# Adafruit_Feather_M0_Adalogger.net
KiCad netlist of a schematic drawn in EAGLE
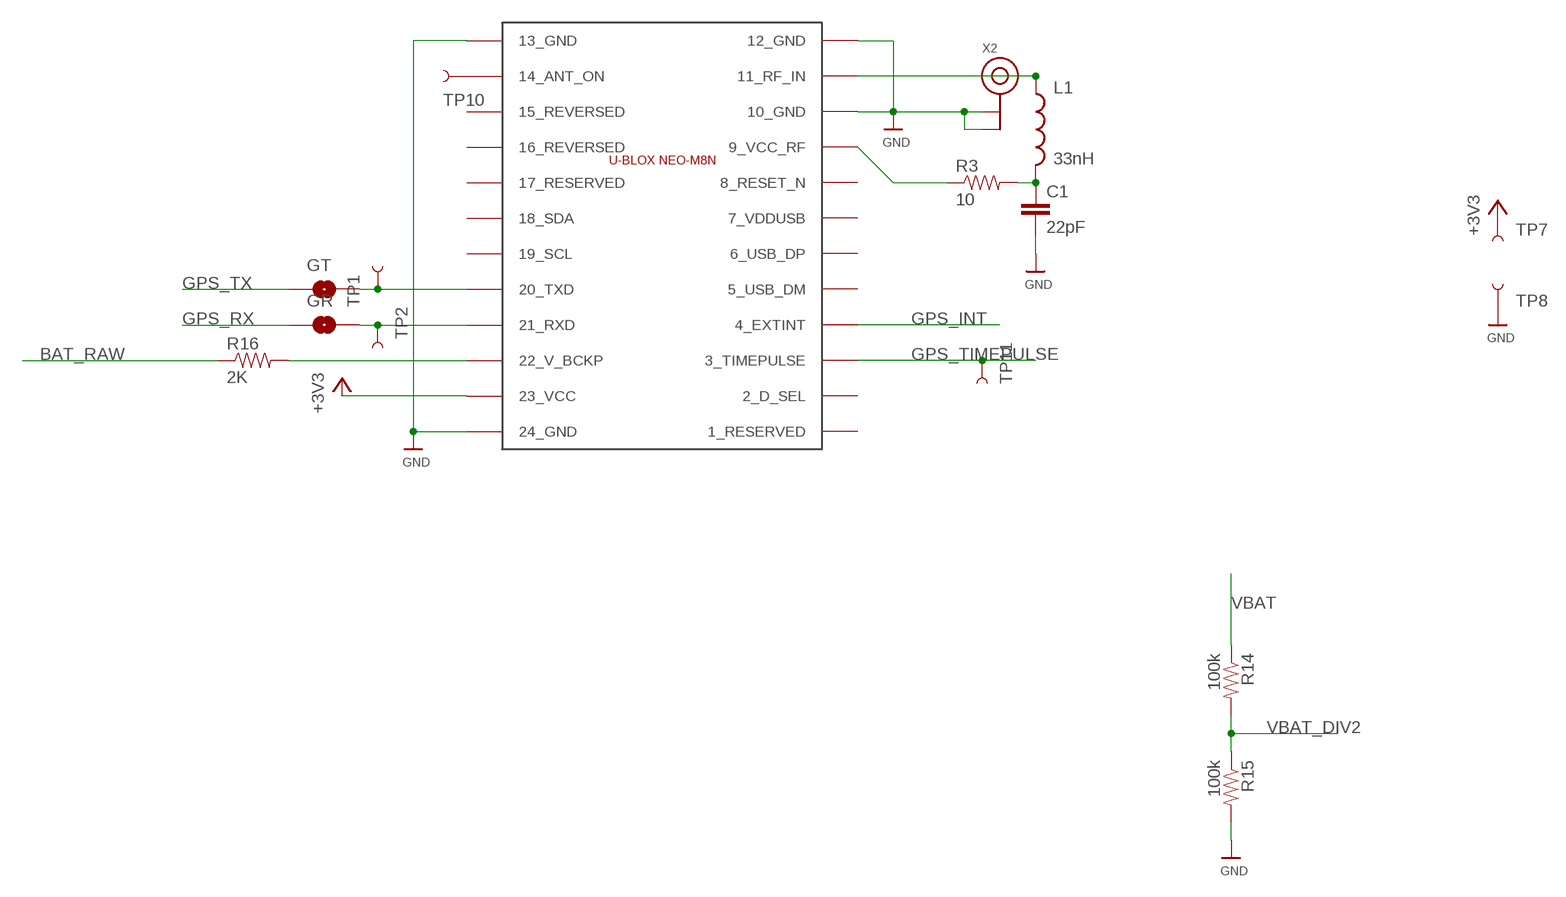
[diagram p0: schematic, sheet 1, part 1 of 2]
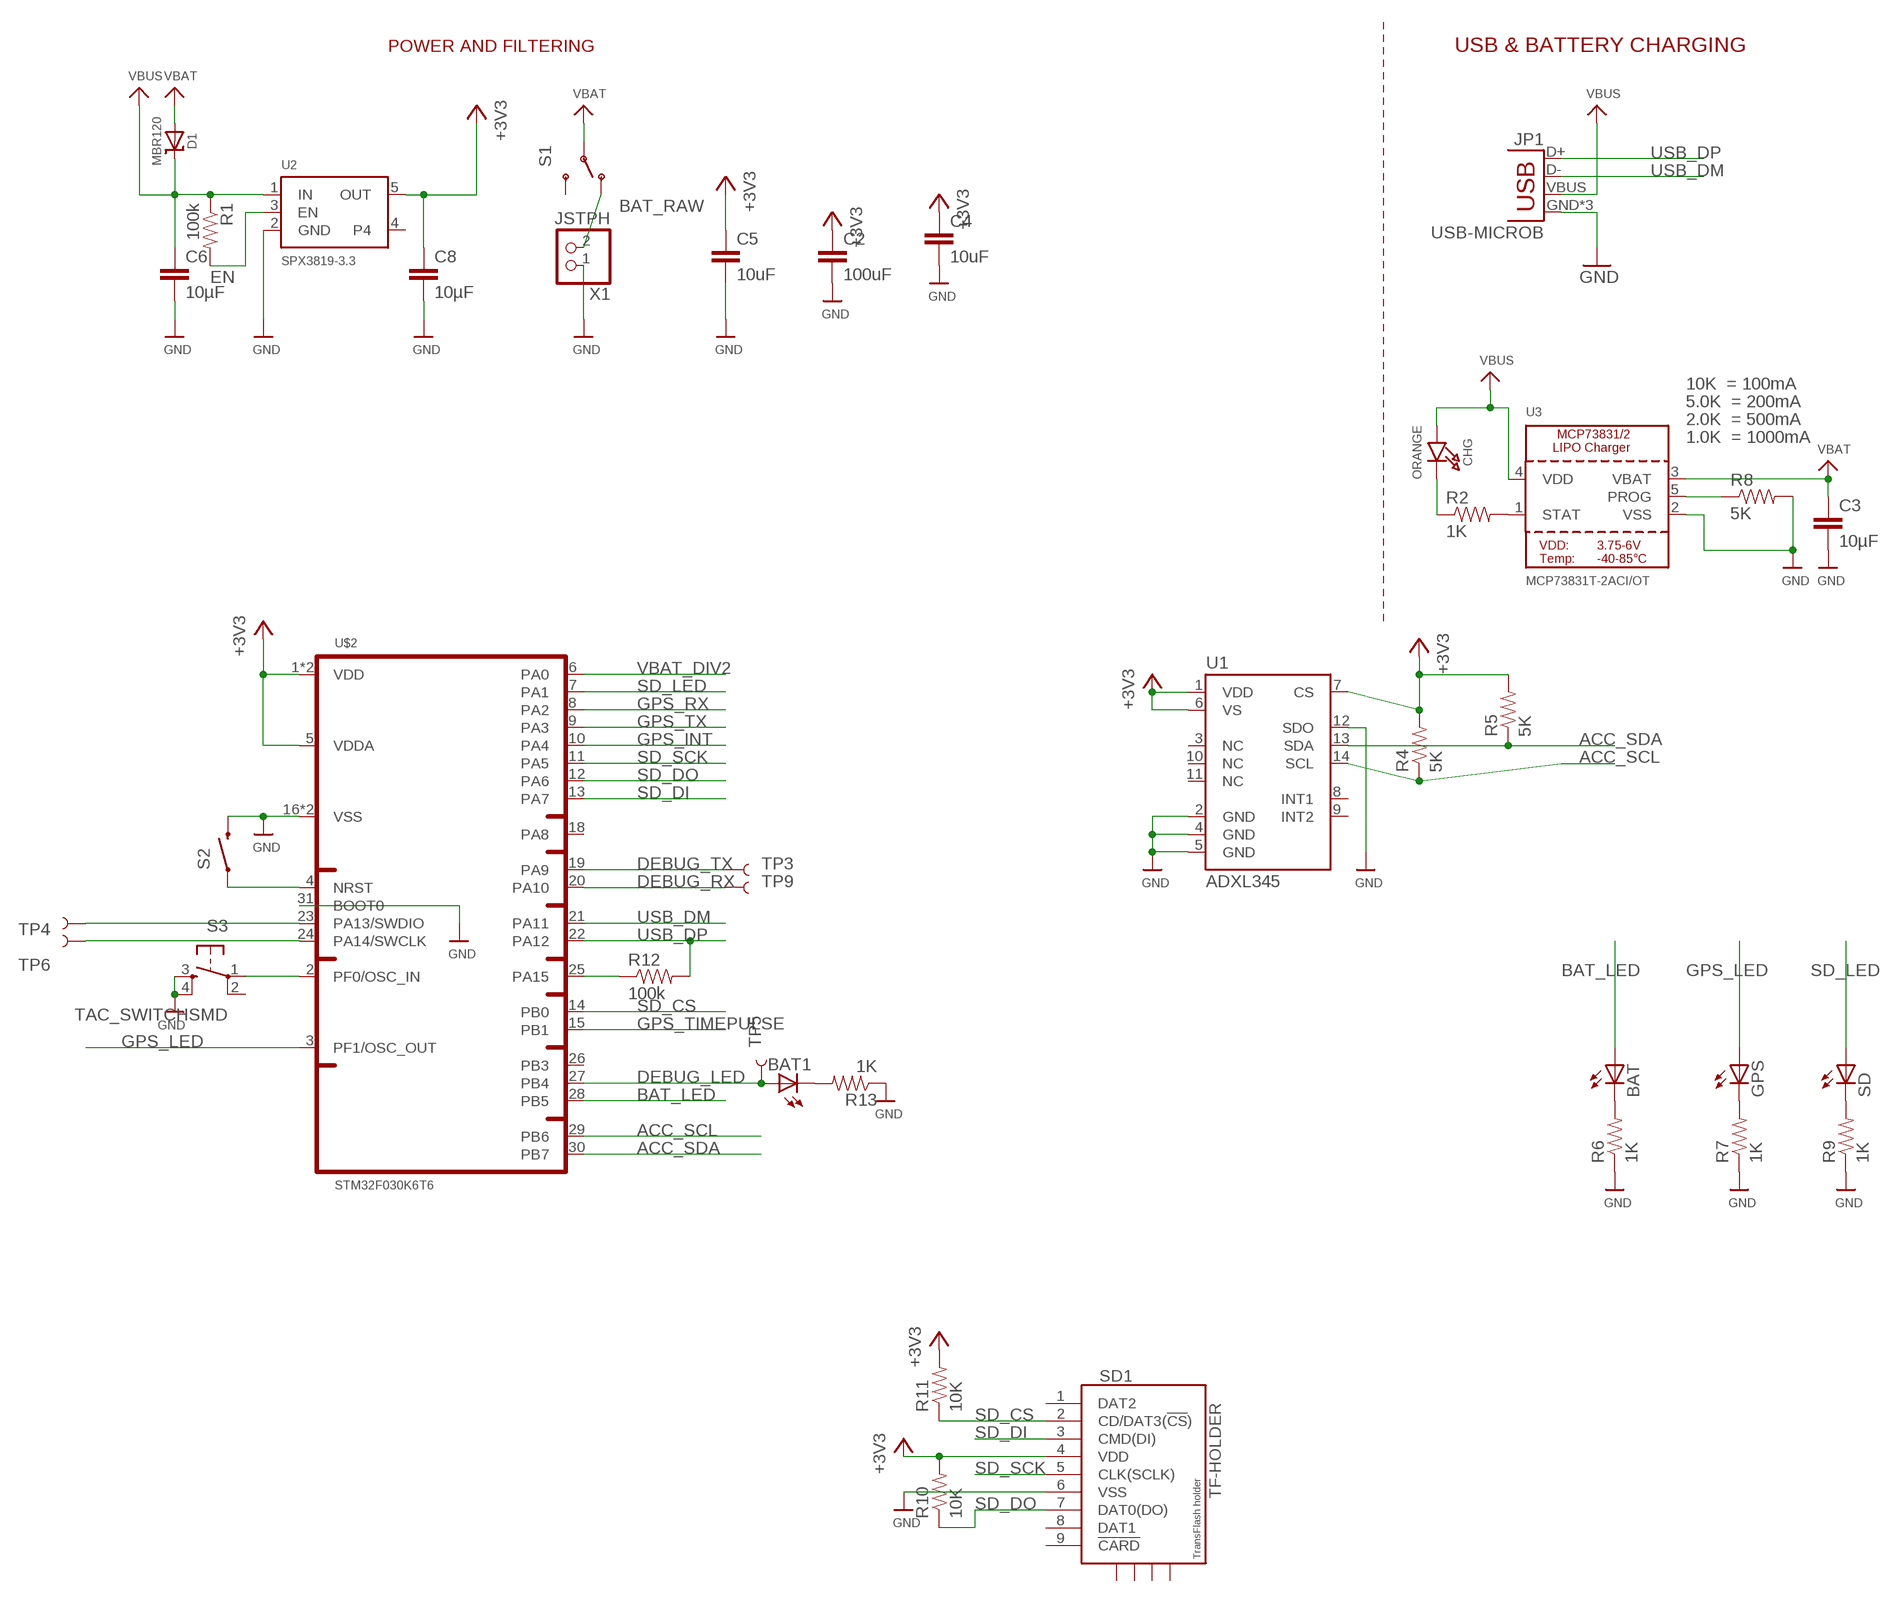
[diagram p1: schematic, sheet 1, part 2 of 2]

(export (version "E")
  (design (tool "Eeschema 10.0.6"))
  (components
    (comp (ref "BAT")
      (value "LEDCHIPLED_0805")
      (footprint "eagle-import:CHIPLED_0805")
      (libsource (lib "eagle-import") (part "LEDCHIPLED_0805"))
    )
    (comp (ref "BAT1")
      (value "LEDCHIPLED_0805")
      (footprint "eagle-import:CHIPLED_0805")
      (libsource (lib "eagle-import") (part "LEDCHIPLED_0805"))
    )
    (comp (ref "C1")
      (value "22pF")
      (footprint "eagle-import:0805")
      (libsource (lib "eagle-import") (part "CAP0805"))
    )
    (comp (ref "C2")
      (value "100uF")
      (footprint "eagle-import:1210")
      (libsource (lib "eagle-import") (part "100UF6.3V20%(1210)"))
    )
    (comp (ref "C3")
      (value "10µF")
      (footprint "eagle-import:0805")
      (libsource (lib "eagle-import") (part "CAP0805"))
    )
    (comp (ref "C4")
      (value "10uF")
      (footprint "eagle-import:0805")
      (libsource (lib "eagle-import") (part "CAP0805"))
    )
    (comp (ref "C5")
      (value "10uF")
      (footprint "eagle-import:0805")
      (libsource (lib "eagle-import") (part "CAP0805"))
    )
    (comp (ref "C6")
      (value "10µF")
      (footprint "eagle-import:0805")
      (libsource (lib "eagle-import") (part "CAP0805"))
    )
    (comp (ref "C8")
      (value "10µF")
      (footprint "eagle-import:0805")
      (libsource (lib "eagle-import") (part "CAP0805"))
    )
    (comp (ref "CHG")
      (value "ORANGE")
      (footprint "eagle-import:CHIPLED_0805_NOOUTLINE")
      (libsource (lib "eagle-import") (part "LED0805_NOOUTLINE"))
    )
    (comp (ref "D1")
      (value "MBR120")
      (footprint "eagle-import:SOD-123")
      (libsource (lib "eagle-import") (part "DIODE-SCHOTTKYSOD-123"))
    )
    (comp (ref "DEKU1")
      (value "UBLOX_NEO-M8N")
      (footprint "eagle-import:UBLOX_NEO-M8N")
      (libsource (lib "eagle-import") (part "UBLOX_NEO-M8N"))
    )
    (comp (ref "GPS")
      (value "LEDCHIPLED_0805")
      (footprint "eagle-import:CHIPLED_0805")
      (libsource (lib "eagle-import") (part "LEDCHIPLED_0805"))
    )
    (comp (ref "GR")
      (value "JUMPER-PAD-2-NO")
      (footprint "eagle-import:PAD-JUMPER-2-NO_NO_SILK")
      (libsource (lib "eagle-import") (part "JUMPER-PAD-2-NO"))
    )
    (comp (ref "GT")
      (value "JUMPER-PAD-2-NO")
      (footprint "eagle-import:PAD-JUMPER-2-NO_NO_SILK")
      (libsource (lib "eagle-import") (part "JUMPER-PAD-2-NO"))
    )
    (comp (ref "JP1")
      (value "USB-MICROB")
      (footprint "eagle-import:USB-MICROB")
      (libsource (lib "eagle-import") (part "USB-MICROB"))
    )
    (comp (ref "L1")
      (value "33nH")
      (footprint "eagle-import:0805")
      (libsource (lib "eagle-import") (part "INDUCTOR0805"))
    )
    (comp (ref "R1")
      (value "100k")
      (footprint "eagle-import:0805")
      (libsource (lib "eagle-import") (part "RESISTOR0805-RES"))
    )
    (comp (ref "R2")
      (value "1K")
      (footprint "eagle-import:0805")
      (libsource (lib "eagle-import") (part "RESISTOR0805-RES"))
    )
    (comp (ref "R3")
      (value "10")
      (footprint "eagle-import:0805")
      (libsource (lib "eagle-import") (part "RESISTOR0805-RES"))
    )
    (comp (ref "R4")
      (value "5K")
      (footprint "eagle-import:0805")
      (libsource (lib "eagle-import") (part "RESISTOR0805-RES"))
    )
    (comp (ref "R5")
      (value "5K")
      (footprint "eagle-import:0805")
      (libsource (lib "eagle-import") (part "RESISTOR0805-RES"))
    )
    (comp (ref "R6")
      (value "1K")
      (footprint "eagle-import:0805")
      (libsource (lib "eagle-import") (part "RESISTOR0805-RES"))
    )
    (comp (ref "R7")
      (value "1K")
      (footprint "eagle-import:0805")
      (libsource (lib "eagle-import") (part "RESISTOR0805-RES"))
    )
    (comp (ref "R8")
      (value "5K")
      (footprint "eagle-import:0805")
      (libsource (lib "eagle-import") (part "RESISTOR0805-RES"))
    )
    (comp (ref "R9")
      (value "1K")
      (footprint "eagle-import:0805")
      (libsource (lib "eagle-import") (part "RESISTOR0805-RES"))
    )
    (comp (ref "R10")
      (value "10K")
      (footprint "eagle-import:0805")
      (libsource (lib "eagle-import") (part "RESISTOR0805-RES"))
    )
    (comp (ref "R11")
      (value "10K")
      (footprint "eagle-import:0805")
      (libsource (lib "eagle-import") (part "RESISTOR0805-RES"))
    )
    (comp (ref "R12")
      (value "100k")
      (footprint "eagle-import:0805")
      (libsource (lib "eagle-import") (part "RESISTOR0805-RES"))
    )
    (comp (ref "R13")
      (value "1K")
      (footprint "eagle-import:0805")
      (libsource (lib "eagle-import") (part "RESISTOR0805-RES"))
    )
    (comp (ref "R14")
      (value "100k")
      (footprint "eagle-import:0805")
      (libsource (lib "eagle-import") (part "RESISTOR0805-RES"))
    )
    (comp (ref "R15")
      (value "100k")
      (footprint "eagle-import:0805")
      (libsource (lib "eagle-import") (part "RESISTOR0805-RES"))
    )
    (comp (ref "R16")
      (value "2K")
      (footprint "eagle-import:0805")
      (libsource (lib "eagle-import") (part "RESISTOR0805-RES"))
    )
    (comp (ref "S1")
      (value "SWITCH-SPDT-SMD-A")
      (footprint "eagle-import:SWITCH-SPST-SMD-A")
      (libsource (lib "eagle-import") (part "SWITCH-SPDT-SMD-A"))
    )
    (comp (ref "S2")
      (value "SWITCH-MOMENTARY-2TURTLE")
      (footprint "eagle-import:KMR2")
      (libsource (lib "eagle-import") (part "SWITCH-MOMENTARY-2TURTLE"))
    )
    (comp (ref "S3")
      (value "TAC_SWITCHSMD")
      (footprint "eagle-import:TACTILE-SWITCH-SMD")
      (libsource (lib "eagle-import") (part "TAC_SWITCHSMD"))
    )
    (comp (ref "SD")
      (value "LEDCHIPLED_0805")
      (footprint "eagle-import:CHIPLED_0805")
      (libsource (lib "eagle-import") (part "LEDCHIPLED_0805"))
    )
    (comp (ref "SD1")
      (value "TF-HOLDER")
      (footprint "eagle-import:TF-PULL")
      (libsource (lib "eagle-import") (part "TF-HOLDER"))
    )
    (comp (ref "TP1")
      (value "TEST-POINT3X5")
      (footprint "eagle-import:PAD.03X.05")
      (libsource (lib "eagle-import") (part "TEST-POINT3X5"))
    )
    (comp (ref "TP2")
      (value "TEST-POINT3X5")
      (footprint "eagle-import:PAD.03X.05")
      (libsource (lib "eagle-import") (part "TEST-POINT3X5"))
    )
    (comp (ref "TP3")
      (value "TEST-POINT3X5")
      (footprint "eagle-import:PAD.03X.05")
      (libsource (lib "eagle-import") (part "TEST-POINT3X5"))
    )
    (comp (ref "TP4")
      (value "TEST-POINT3X5")
      (footprint "eagle-import:PAD.03X.05")
      (libsource (lib "eagle-import") (part "TEST-POINT3X5"))
    )
    (comp (ref "TP5")
      (value "TEST-POINT3X5")
      (footprint "eagle-import:PAD.03X.05")
      (libsource (lib "eagle-import") (part "TEST-POINT3X5"))
    )
    (comp (ref "TP6")
      (value "TEST-POINT3X5")
      (footprint "eagle-import:PAD.03X.05")
      (libsource (lib "eagle-import") (part "TEST-POINT3X5"))
    )
    (comp (ref "TP7")
      (value "TEST-POINT3X5")
      (footprint "eagle-import:PAD.03X.05")
      (libsource (lib "eagle-import") (part "TEST-POINT3X5"))
    )
    (comp (ref "TP8")
      (value "TEST-POINT3X5")
      (footprint "eagle-import:PAD.03X.05")
      (libsource (lib "eagle-import") (part "TEST-POINT3X5"))
    )
    (comp (ref "TP9")
      (value "TEST-POINT3X5")
      (footprint "eagle-import:PAD.03X.05")
      (libsource (lib "eagle-import") (part "TEST-POINT3X5"))
    )
    (comp (ref "TP10")
      (value "TEST-POINT3X5")
      (footprint "eagle-import:PAD.03X.05")
      (libsource (lib "eagle-import") (part "TEST-POINT3X5"))
    )
    (comp (ref "TP11")
      (value "TEST-POINT3X5")
      (footprint "eagle-import:PAD.03X.05")
      (libsource (lib "eagle-import") (part "TEST-POINT3X5"))
    )
    (comp (ref "U$2")
      (value "STM32F030K6T6")
      (footprint "eagle-import:TQFP32-08")
      (libsource (lib "eagle-import") (part "STM32F030K6T6"))
    )
    (comp (ref "U1")
      (value "ADXL345")
      (footprint "eagle-import:LGA14")
      (libsource (lib "eagle-import") (part "ADXL345"))
    )
    (comp (ref "U2")
      (value "SPX3819-3.3")
      (footprint "eagle-import:SOT23-5")
      (libsource (lib "eagle-import") (part "VREG_SOT23-5"))
    )
    (comp (ref "U3")
      (value "MCP73831T-2ACI/OT")
      (footprint "eagle-import:SOT23-5")
      (libsource (lib "eagle-import") (part "MCP73831/2"))
    )
    (comp (ref "X1")
      (value "JSTPH")
      (footprint "eagle-import:JSTPH2")
      (libsource (lib "eagle-import") (part "CON_JST_PH_2PIN"))
    )
    (comp (ref "X2")
      (value "ANTENNA_U.FL")
      (footprint "eagle-import:U.FL")
      (libsource (lib "eagle-import") (part "ANTENNA_U.FL"))
    )
  )
  (nets
    (net (code "1") (name "+3V3") (class "Default")
      (node (ref "C2") (pin "1") (pinfunction "1_1") (pintype "passive"))
      (node (ref "C4") (pin "1") (pinfunction "1_1") (pintype "passive"))
      (node (ref "C5") (pin "1") (pinfunction "1_1") (pintype "passive"))
      (node (ref "C8") (pin "1") (pinfunction "1_1") (pintype "passive"))
      (node (ref "DEKU1") (pin "23_VCC") (pinfunction "23_VCC_23_VCC") (pintype "bidirectional"))
      (node (ref "R10") (pin "2") (pinfunction "2_2") (pintype "passive"))
      (node (ref "R11") (pin "2") (pinfunction "2_2") (pintype "passive"))
      (node (ref "R4") (pin "2") (pinfunction "2_2") (pintype "passive"))
      (node (ref "R5") (pin "2") (pinfunction "2_2") (pintype "passive"))
      (node (ref "SD1") (pin "4") (pinfunction "VDD_4") (pintype "power_in"))
      (node (ref "TP7") (pin "P$1") (pinfunction "1_P$1") (pintype "bidirectional"))
      (node (ref "U$2") (pin "1") (pinfunction "VDD_1") (pintype "bidirectional"))
      (node (ref "U$2") (pin "17") (pinfunction "VDD_17") (pintype "bidirectional"))
      (node (ref "U$2") (pin "5") (pinfunction "VDDA_5") (pintype "bidirectional"))
      (node (ref "U1") (pin "1") (pinfunction "VDD_1") (pintype "bidirectional"))
      (node (ref "U1") (pin "6") (pinfunction "VS_6") (pintype "bidirectional"))
      (node (ref "U1") (pin "7") (pinfunction "CS_7") (pintype "bidirectional"))
      (node (ref "U2") (pin "5") (pinfunction "OUT_5") (pintype "power_in"))
    )
    (net (code "2") (name "/ACC_SCL") (class "Default")
      (node (ref "R4") (pin "1") (pinfunction "1_1") (pintype "passive"))
      (node (ref "U$2") (pin "29") (pinfunction "PB6_29") (pintype "bidirectional"))
      (node (ref "U1") (pin "14") (pinfunction "SCL_14") (pintype "bidirectional"))
    )
    (net (code "3") (name "/ACC_SDA") (class "Default")
      (node (ref "R5") (pin "1") (pinfunction "1_1") (pintype "passive"))
      (node (ref "U$2") (pin "30") (pinfunction "PB7_30") (pintype "bidirectional"))
      (node (ref "U1") (pin "13") (pinfunction "SDA_13") (pintype "bidirectional"))
    )
    (net (code "4") (name "/BAT_LED") (class "Default")
      (node (ref "BAT") (pin "A") (pinfunction "A_A") (pintype "passive"))
      (node (ref "U$2") (pin "28") (pinfunction "PB5_28") (pintype "bidirectional"))
    )
    (net (code "5") (name "/BAT_RAW") (class "Default")
      (node (ref "R16") (pin "1") (pinfunction "1_1") (pintype "passive"))
      (node (ref "S1") (pin "1") (pinfunction "O_1") (pintype "passive"))
      (node (ref "X1") (pin "2") (pinfunction "2_2") (pintype "passive"))
    )
    (net (code "6") (name "/DEBUG_LED") (class "Default")
      (node (ref "BAT1") (pin "A") (pinfunction "A_A") (pintype "passive"))
      (node (ref "TP5") (pin "P$1") (pinfunction "1_P$1") (pintype "bidirectional"))
      (node (ref "U$2") (pin "27") (pinfunction "PB4_27") (pintype "bidirectional"))
    )
    (net (code "7") (name "/DEBUG_RX") (class "Default")
      (node (ref "TP9") (pin "P$1") (pinfunction "1_P$1") (pintype "bidirectional"))
      (node (ref "U$2") (pin "20") (pinfunction "PA10_20") (pintype "bidirectional"))
    )
    (net (code "8") (name "/DEBUG_TX") (class "Default")
      (node (ref "TP3") (pin "P$1") (pinfunction "1_P$1") (pintype "bidirectional"))
      (node (ref "U$2") (pin "19") (pinfunction "PA9_19") (pintype "bidirectional"))
    )
    (net (code "9") (name "/EN") (class "Default")
      (node (ref "R1") (pin "2") (pinfunction "2_2") (pintype "passive"))
      (node (ref "U2") (pin "3") (pinfunction "EN_3") (pintype "input"))
    )
    (net (code "10") (name "/GPS_INT") (class "Default")
      (node (ref "DEKU1") (pin "4_EXTINT") (pinfunction "4_EXTINT_4_EXTINT") (pintype "bidirectional"))
      (node (ref "U$2") (pin "10") (pinfunction "PA4_10") (pintype "bidirectional"))
    )
    (net (code "11") (name "/GPS_LED") (class "Default")
      (node (ref "GPS") (pin "A") (pinfunction "A_A") (pintype "passive"))
      (node (ref "U$2") (pin "3") (pinfunction "PF1/OSC_OUT_3") (pintype "bidirectional"))
    )
    (net (code "12") (name "/GPS_RX") (class "Default")
      (node (ref "GR") (pin "1") (pinfunction "1_1") (pintype "passive"))
      (node (ref "U$2") (pin "8") (pinfunction "PA2_8") (pintype "bidirectional"))
    )
    (net (code "13") (name "/GPS_TIMEPULSE") (class "Default")
      (node (ref "DEKU1") (pin "3_TIMEPULSE") (pinfunction "3_TIMEPULSE_3_TIMEPULSE") (pintype "bidirectional"))
      (node (ref "TP11") (pin "P$1") (pinfunction "1_P$1") (pintype "bidirectional"))
      (node (ref "U$2") (pin "15") (pinfunction "PB1_15") (pintype "bidirectional"))
    )
    (net (code "14") (name "/GPS_TX") (class "Default")
      (node (ref "GT") (pin "1") (pinfunction "1_1") (pintype "passive"))
      (node (ref "U$2") (pin "9") (pinfunction "PA3_9") (pintype "bidirectional"))
    )
    (net (code "15") (name "/SD_CS") (class "Default")
      (node (ref "R11") (pin "1") (pinfunction "1_1") (pintype "passive"))
      (node (ref "SD1") (pin "2") (pinfunction "CD/DAT3(~{CS})_2") (pintype "bidirectional"))
      (node (ref "U$2") (pin "14") (pinfunction "PB0_14") (pintype "bidirectional"))
    )
    (net (code "16") (name "/SD_DI") (class "Default")
      (node (ref "SD1") (pin "3") (pinfunction "CMD(DI)_3") (pintype "bidirectional"))
      (node (ref "U$2") (pin "13") (pinfunction "PA7_13") (pintype "bidirectional"))
    )
    (net (code "17") (name "/SD_DO") (class "Default")
      (node (ref "R10") (pin "1") (pinfunction "1_1") (pintype "passive"))
      (node (ref "SD1") (pin "7") (pinfunction "DAT0(DO)_7") (pintype "bidirectional"))
      (node (ref "U$2") (pin "12") (pinfunction "PA6_12") (pintype "bidirectional"))
    )
    (net (code "18") (name "/SD_LED") (class "Default")
      (node (ref "SD") (pin "A") (pinfunction "A_A") (pintype "passive"))
      (node (ref "U$2") (pin "7") (pinfunction "PA1_7") (pintype "bidirectional"))
    )
    (net (code "19") (name "/SD_SCK") (class "Default")
      (node (ref "SD1") (pin "5") (pinfunction "CLK(SCLK)_5") (pintype "input"))
      (node (ref "U$2") (pin "11") (pinfunction "PA5_11") (pintype "bidirectional"))
    )
    (net (code "20") (name "/USB_DM") (class "Default")
      (node (ref "JP1") (pin "D-") (pinfunction "D-_D-") (pintype "bidirectional"))
      (node (ref "U$2") (pin "21") (pinfunction "PA11_21") (pintype "bidirectional"))
    )
    (net (code "21") (name "/USB_DP") (class "Default")
      (node (ref "JP1") (pin "D+") (pinfunction "D+_D+") (pintype "bidirectional"))
      (node (ref "R12") (pin "2") (pinfunction "2_2") (pintype "passive"))
      (node (ref "U$2") (pin "22") (pinfunction "PA12_22") (pintype "bidirectional"))
    )
    (net (code "22") (name "/VBAT_DIV2") (class "Default")
      (node (ref "R14") (pin "2") (pinfunction "2_2") (pintype "passive"))
      (node (ref "R15") (pin "1") (pinfunction "1_1") (pintype "passive"))
      (node (ref "U$2") (pin "6") (pinfunction "PA0_6") (pintype "bidirectional"))
    )
    (net (code "23") (name "GND") (class "Default")
      (node (ref "C1") (pin "2") (pinfunction "2_2") (pintype "passive"))
      (node (ref "C2") (pin "2") (pinfunction "2_2") (pintype "passive"))
      (node (ref "C3") (pin "2") (pinfunction "2_2") (pintype "passive"))
      (node (ref "C4") (pin "2") (pinfunction "2_2") (pintype "passive"))
      (node (ref "C5") (pin "2") (pinfunction "2_2") (pintype "passive"))
      (node (ref "C6") (pin "2") (pinfunction "2_2") (pintype "passive"))
      (node (ref "C8") (pin "2") (pinfunction "2_2") (pintype "passive"))
      (node (ref "DEKU1") (pin "10_GND") (pinfunction "10_GND_10_GND") (pintype "bidirectional"))
      (node (ref "DEKU1") (pin "12_GND") (pinfunction "12_GND_12_GND") (pintype "bidirectional"))
      (node (ref "DEKU1") (pin "13_GND") (pinfunction "13_GND_13_GND") (pintype "bidirectional"))
      (node (ref "DEKU1") (pin "24_GND") (pinfunction "24_GND_24_GND") (pintype "bidirectional"))
      (node (ref "JP1") (pin "GND") (pinfunction "GND_GND") (pintype "bidirectional"))
      (node (ref "JP1") (pin "MT1") (pinfunction "GND_MT1") (pintype "bidirectional"))
      (node (ref "JP1") (pin "MT2") (pinfunction "GND_MT2") (pintype "bidirectional"))
      (node (ref "R13") (pin "1") (pinfunction "1_1") (pintype "passive"))
      (node (ref "R15") (pin "2") (pinfunction "2_2") (pintype "passive"))
      (node (ref "R6") (pin "1") (pinfunction "1_1") (pintype "passive"))
      (node (ref "R7") (pin "1") (pinfunction "1_1") (pintype "passive"))
      (node (ref "R8") (pin "2") (pinfunction "2_2") (pintype "passive"))
      (node (ref "R9") (pin "1") (pinfunction "1_1") (pintype "passive"))
      (node (ref "S2") (pin "3") (pinfunction "2_3") (pintype "passive"))
      (node (ref "S3") (pin "3") (pinfunction "3_3") (pintype "passive"))
      (node (ref "S3") (pin "4") (pinfunction "4_4") (pintype "passive"))
      (node (ref "SD1") (pin "6") (pinfunction "VSS_6") (pintype "power_in"))
      (node (ref "TP8") (pin "P$1") (pinfunction "1_P$1") (pintype "bidirectional"))
      (node (ref "U$2") (pin "16") (pinfunction "VSS_16") (pintype "bidirectional"))
      (node (ref "U$2") (pin "31") (pinfunction "BOOT0_31") (pintype "bidirectional"))
      (node (ref "U$2") (pin "32") (pinfunction "VSS_32") (pintype "bidirectional"))
      (node (ref "U1") (pin "12") (pinfunction "SDO_12") (pintype "bidirectional"))
      (node (ref "U1") (pin "2") (pinfunction "GND_2") (pintype "bidirectional"))
      (node (ref "U1") (pin "4") (pinfunction "GND_4") (pintype "bidirectional"))
      (node (ref "U1") (pin "5") (pinfunction "GND_5") (pintype "bidirectional"))
      (node (ref "U2") (pin "2") (pinfunction "GND_2") (pintype "power_in"))
      (node (ref "U3") (pin "2") (pinfunction "VSS_2") (pintype "power_in"))
      (node (ref "X1") (pin "1") (pinfunction "1_1") (pintype "passive"))
      (node (ref "X2") (pin "1") (pinfunction "GND_1") (pintype "passive"))
      (node (ref "X2") (pin "2") (pinfunction "GND_2") (pintype "passive"))
    )
    (net (code "24") (name "Net-(BAT-PadC)") (class "Default")
      (node (ref "BAT") (pin "C") (pinfunction "C_C") (pintype "passive"))
      (node (ref "R6") (pin "2") (pinfunction "2_2") (pintype "passive"))
    )
    (net (code "25") (name "Net-(BAT1-PadC)") (class "Default")
      (node (ref "BAT1") (pin "C") (pinfunction "C_C") (pintype "passive"))
      (node (ref "R13") (pin "2") (pinfunction "2_2") (pintype "passive"))
    )
    (net (code "26") (name "Net-(C1-Pad1)") (class "Default")
      (node (ref "C1") (pin "1") (pinfunction "1_1") (pintype "passive"))
      (node (ref "L1") (pin "2") (pinfunction "2_2") (pintype "passive"))
      (node (ref "R3") (pin "2") (pinfunction "2_2") (pintype "passive"))
    )
    (net (code "27") (name "Net-(CHG-PadC)") (class "Default")
      (node (ref "CHG") (pin "C") (pinfunction "C_C") (pintype "passive"))
      (node (ref "R2") (pin "1") (pinfunction "1_1") (pintype "passive"))
    )
    (net (code "28") (name "Net-(DEKU1-Pad9_VCC_RF)") (class "Default")
      (node (ref "DEKU1") (pin "9_VCC_RF") (pinfunction "9_VCC_RF_9_VCC_RF") (pintype "bidirectional"))
      (node (ref "R3") (pin "1") (pinfunction "1_1") (pintype "passive"))
    )
    (net (code "29") (name "Net-(DEKU1-Pad22_V_BCKP)") (class "Default")
      (node (ref "DEKU1") (pin "22_V_BCKP") (pinfunction "22_V_BCKP_22_V_BCKP") (pintype "bidirectional"))
      (node (ref "R16") (pin "2") (pinfunction "2_2") (pintype "passive"))
    )
    (net (code "30") (name "Net-(GPS-PadC)") (class "Default")
      (node (ref "GPS") (pin "C") (pinfunction "C_C") (pintype "passive"))
      (node (ref "R7") (pin "2") (pinfunction "2_2") (pintype "passive"))
    )
    (net (code "31") (name "Net-(R9-Pad2)") (class "Default")
      (node (ref "R9") (pin "2") (pinfunction "2_2") (pintype "passive"))
      (node (ref "SD") (pin "C") (pinfunction "C_C") (pintype "passive"))
    )
    (net (code "32") (name "Net-(TP1-1)") (class "Default")
      (node (ref "DEKU1") (pin "20_TXD") (pinfunction "20_TXD_20_TXD") (pintype "bidirectional"))
      (node (ref "GT") (pin "2") (pinfunction "2_2") (pintype "passive"))
      (node (ref "TP1") (pin "P$1") (pinfunction "1_P$1") (pintype "bidirectional"))
    )
    (net (code "33") (name "Net-(TP2-1)") (class "Default")
      (node (ref "DEKU1") (pin "21_RXD") (pinfunction "21_RXD_21_RXD") (pintype "bidirectional"))
      (node (ref "GR") (pin "2") (pinfunction "2_2") (pintype "passive"))
      (node (ref "TP2") (pin "P$1") (pinfunction "1_P$1") (pintype "bidirectional"))
    )
    (net (code "34") (name "Net-(TP4-1)") (class "Default")
      (node (ref "TP4") (pin "P$1") (pinfunction "1_P$1") (pintype "bidirectional"))
      (node (ref "U$2") (pin "23") (pinfunction "PA13/SWDIO_23") (pintype "bidirectional"))
    )
    (net (code "35") (name "Net-(TP6-1)") (class "Default")
      (node (ref "TP6") (pin "P$1") (pinfunction "1_P$1") (pintype "bidirectional"))
      (node (ref "U$2") (pin "24") (pinfunction "PA14/SWCLK_24") (pintype "bidirectional"))
    )
    (net (code "36") (name "Net-(TP10-1)") (class "Default")
      (node (ref "DEKU1") (pin "14_ANT_ON") (pinfunction "14_ANT_ON_14_ANT_ON") (pintype "bidirectional"))
      (node (ref "TP10") (pin "P$1") (pinfunction "1_P$1") (pintype "bidirectional"))
    )
    (net (code "37") (name "Net-(U$2-NRST)") (class "Default")
      (node (ref "S2") (pin "1") (pinfunction "1_1") (pintype "passive"))
      (node (ref "U$2") (pin "4") (pinfunction "NRST_4") (pintype "bidirectional"))
    )
    (net (code "38") (name "Net-(U$2-PA15)") (class "Default")
      (node (ref "R12") (pin "1") (pinfunction "1_1") (pintype "passive"))
      (node (ref "U$2") (pin "25") (pinfunction "PA15_25") (pintype "bidirectional"))
    )
    (net (code "39") (name "Net-(U$2-PF0{slash}OSC_IN)") (class "Default")
      (node (ref "S3") (pin "1") (pinfunction "1_1") (pintype "passive"))
      (node (ref "U$2") (pin "2") (pinfunction "PF0/OSC_IN_2") (pintype "bidirectional"))
    )
    (net (code "40") (name "Net-(U3-PROG)") (class "Default")
      (node (ref "R8") (pin "1") (pinfunction "1_1") (pintype "passive"))
      (node (ref "U3") (pin "5") (pinfunction "PROG_5") (pintype "input"))
    )
    (net (code "41") (name "Net-(U3-STAT)") (class "Default")
      (node (ref "R2") (pin "2") (pinfunction "2_2") (pintype "passive"))
      (node (ref "U3") (pin "1") (pinfunction "STAT_1") (pintype "output"))
    )
    (net (code "42") (name "Net-(X2-SIGNAL)") (class "Default")
      (node (ref "DEKU1") (pin "11_RF_IN") (pinfunction "11_RF_IN_11_RF_IN") (pintype "bidirectional"))
      (node (ref "L1") (pin "1") (pinfunction "1_1") (pintype "passive"))
      (node (ref "X2") (pin "3") (pinfunction "SIGNAL_3") (pintype "passive"))
    )
    (net (code "43") (name "VBAT") (class "Default")
      (node (ref "C3") (pin "1") (pinfunction "1_1") (pintype "passive"))
      (node (ref "D1") (pin "A") (pinfunction "A_A") (pintype "passive"))
      (node (ref "R14") (pin "1") (pinfunction "1_1") (pintype "passive"))
      (node (ref "S1") (pin "2") (pinfunction "P_2") (pintype "passive"))
      (node (ref "U3") (pin "3") (pinfunction "VBAT_3") (pintype "power_in"))
    )
    (net (code "44") (name "VBUS") (class "Default")
      (node (ref "C6") (pin "1") (pinfunction "1_1") (pintype "passive"))
      (node (ref "CHG") (pin "A") (pinfunction "A_A") (pintype "passive"))
      (node (ref "D1") (pin "C") (pinfunction "C_C") (pintype "passive"))
      (node (ref "JP1") (pin "VBUS") (pinfunction "VBUS_VBUS") (pintype "bidirectional"))
      (node (ref "R1") (pin "1") (pinfunction "1_1") (pintype "passive"))
      (node (ref "U2") (pin "1") (pinfunction "IN_1") (pintype "power_in"))
      (node (ref "U3") (pin "4") (pinfunction "VDD_4") (pintype "power_in"))
    )
    (net (code "45") (name "unconnected-(DEKU1-Pad1_RESERVED)") (class "Default")
      (node (ref "DEKU1") (pin "1_RESERVED") (pinfunction "1_RESERVED_1_RESERVED") (pintype "bidirectional"))
    )
    (net (code "46") (name "unconnected-(DEKU1-Pad2_D_SEL)") (class "Default")
      (node (ref "DEKU1") (pin "2_D_SEL") (pinfunction "2_D_SEL_2_D_SEL") (pintype "bidirectional"))
    )
    (net (code "47") (name "unconnected-(DEKU1-Pad5_USB_DM)") (class "Default")
      (node (ref "DEKU1") (pin "5_USB_DM") (pinfunction "5_USB_DM_5_USB_DM") (pintype "bidirectional"))
    )
    (net (code "48") (name "unconnected-(DEKU1-Pad6_USB_DP)") (class "Default")
      (node (ref "DEKU1") (pin "6_USB_DP") (pinfunction "6_USB_DP_6_USB_DP") (pintype "bidirectional"))
    )
    (net (code "49") (name "unconnected-(DEKU1-Pad7_VDDUSB)") (class "Default")
      (node (ref "DEKU1") (pin "7_VDDUSB") (pinfunction "7_VDDUSB_7_VDDUSB") (pintype "bidirectional"))
    )
    (net (code "50") (name "unconnected-(DEKU1-Pad8_RESET_N)") (class "Default")
      (node (ref "DEKU1") (pin "8_RESET_N") (pinfunction "8_RESET_N_8_RESET_N") (pintype "bidirectional"))
    )
    (net (code "51") (name "unconnected-(DEKU1-Pad15_REVERSED)") (class "Default")
      (node (ref "DEKU1") (pin "15_REVERSED") (pinfunction "15_REVERSED_15_REVERSED") (pintype "bidirectional"))
    )
    (net (code "52") (name "unconnected-(DEKU1-Pad16_REVERSED)") (class "Default")
      (node (ref "DEKU1") (pin "16_REVERSED") (pinfunction "16_REVERSED_16_REVERSED") (pintype "bidirectional"))
    )
    (net (code "53") (name "unconnected-(DEKU1-Pad17_RESERVED)") (class "Default")
      (node (ref "DEKU1") (pin "17_RESERVED") (pinfunction "17_RESERVED_17_RESERVED") (pintype "bidirectional"))
    )
    (net (code "54") (name "unconnected-(DEKU1-Pad18_SDA)") (class "Default")
      (node (ref "DEKU1") (pin "18_SDA") (pinfunction "18_SDA_18_SDA") (pintype "bidirectional"))
    )
    (net (code "55") (name "unconnected-(DEKU1-Pad19_SCL)") (class "Default")
      (node (ref "DEKU1") (pin "19_SCL") (pinfunction "19_SCL_19_SCL") (pintype "bidirectional"))
    )
    (net (code "56") (name "unconnected-(S1-S-Pad3)") (class "Default")
      (node (ref "S1") (pin "3") (pinfunction "S_3") (pintype "passive"))
    )
    (net (code "57") (name "unconnected-(S3-Pad2)") (class "Default")
      (node (ref "S3") (pin "2") (pinfunction "2_2") (pintype "passive"))
    )
    (net (code "58") (name "unconnected-(SD1-DAT1-Pad8)") (class "Default")
      (node (ref "SD1") (pin "8") (pinfunction "DAT1_8") (pintype "bidirectional"))
    )
    (net (code "59") (name "unconnected-(SD1-DAT2-Pad1)") (class "Default")
      (node (ref "SD1") (pin "1") (pinfunction "DAT2_1") (pintype "bidirectional"))
    )
    (net (code "60") (name "unconnected-(SD1-PadS1)") (class "Default")
      (node (ref "SD1") (pin "S1") (pinfunction "S1_S1") (pintype "passive"))
    )
    (net (code "61") (name "unconnected-(SD1-PadS2)") (class "Default")
      (node (ref "SD1") (pin "S2") (pinfunction "S2_S2") (pintype "passive"))
    )
    (net (code "62") (name "unconnected-(SD1-PadS3)") (class "Default")
      (node (ref "SD1") (pin "S3") (pinfunction "S3_S3") (pintype "passive"))
    )
    (net (code "63") (name "unconnected-(SD1-PadS4)") (class "Default")
      (node (ref "SD1") (pin "S4") (pinfunction "S4_S4") (pintype "passive"))
    )
    (net (code "64") (name "unconnected-(SD1-~{CARD}-Pad9)") (class "Default")
      (node (ref "SD1") (pin "9") (pinfunction "~{CARD}_9") (pintype "passive"))
    )
    (net (code "65") (name "unconnected-(U$2-PA8-Pad18)") (class "Default")
      (node (ref "U$2") (pin "18") (pinfunction "PA8_18") (pintype "bidirectional"))
    )
    (net (code "66") (name "unconnected-(U$2-PB3-Pad26)") (class "Default")
      (node (ref "U$2") (pin "26") (pinfunction "PB3_26") (pintype "bidirectional"))
    )
    (net (code "67") (name "unconnected-(U1-INT1-Pad8)") (class "Default")
      (node (ref "U1") (pin "8") (pinfunction "INT1_8") (pintype "bidirectional"))
    )
    (net (code "68") (name "unconnected-(U1-INT2-Pad9)") (class "Default")
      (node (ref "U1") (pin "9") (pinfunction "INT2_9") (pintype "bidirectional"))
    )
    (net (code "69") (name "unconnected-(U1-NC-Pad3)") (class "Default")
      (node (ref "U1") (pin "3") (pinfunction "NC_3") (pintype "bidirectional"))
    )
    (net (code "70") (name "unconnected-(U1-NC-Pad10)") (class "Default")
      (node (ref "U1") (pin "10") (pinfunction "NC_10") (pintype "bidirectional"))
    )
    (net (code "71") (name "unconnected-(U1-NC-Pad11)") (class "Default")
      (node (ref "U1") (pin "11") (pinfunction "NC_11") (pintype "bidirectional"))
    )
    (net (code "72") (name "unconnected-(U2-P4-Pad4)") (class "Default")
      (node (ref "U2") (pin "4") (pinfunction "P4_4") (pintype "bidirectional"))
    )
  )
)
